# ESP-Power.net
KiCad netlist of a schematic drawn in Altium Designer
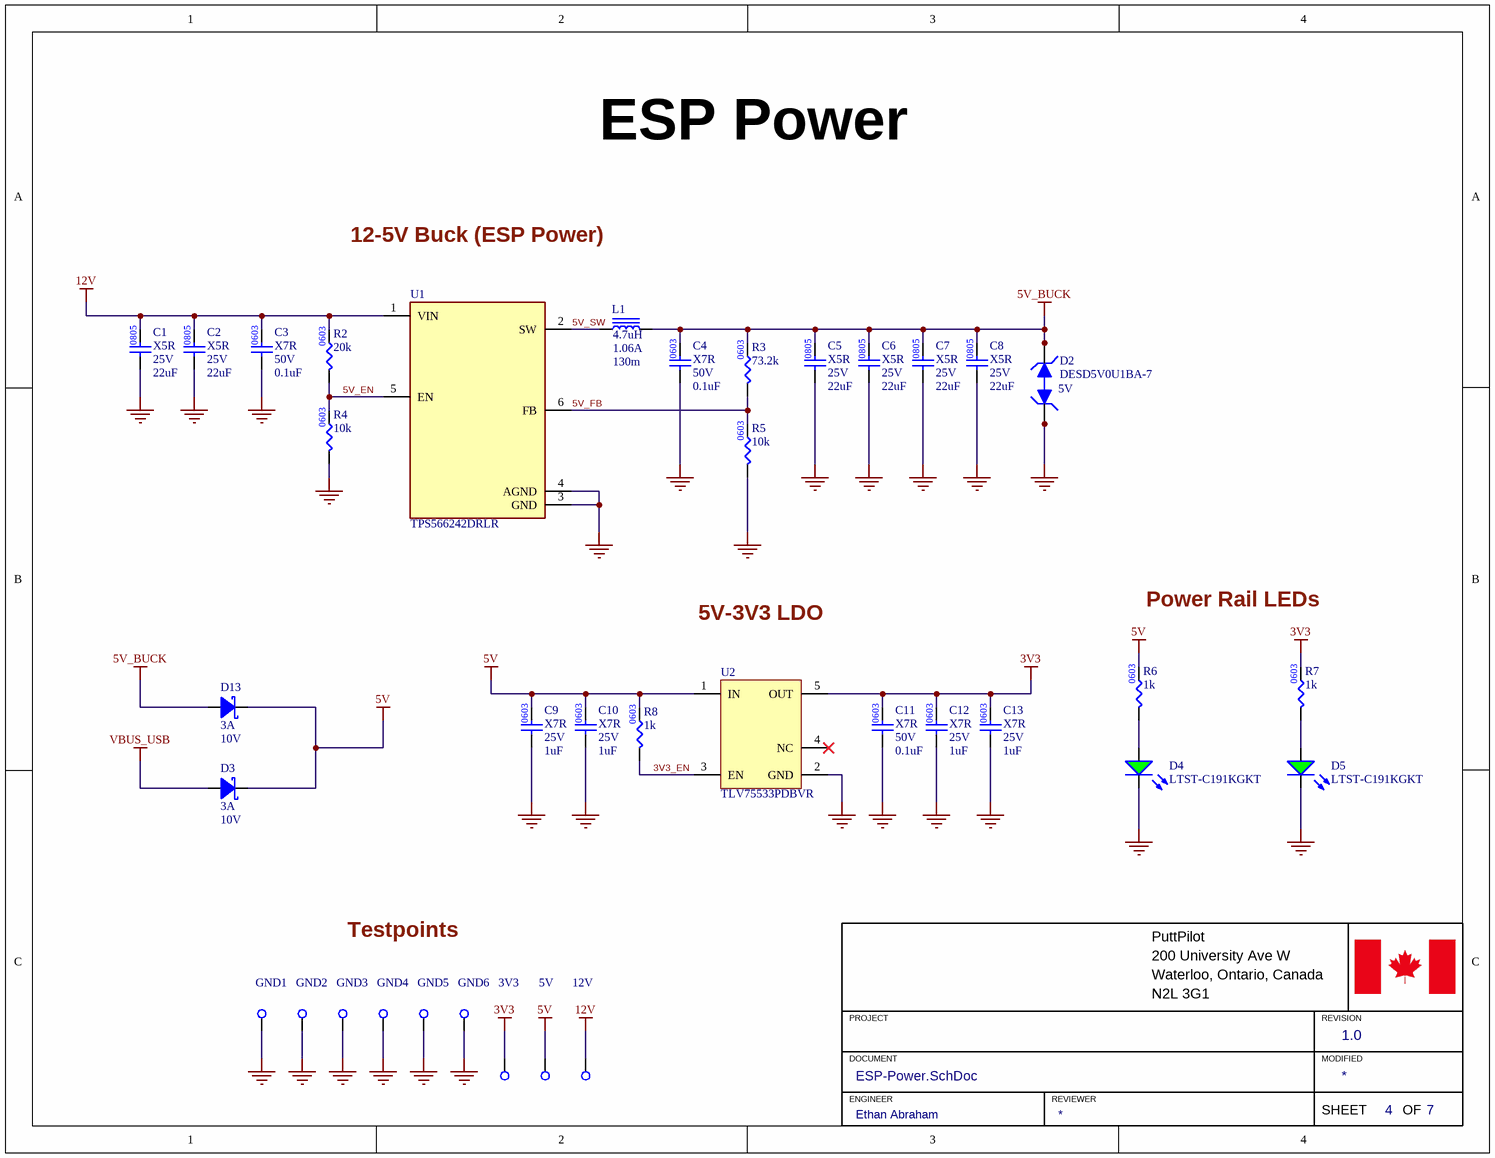
[diagram p0: ESP-Power.SchDoc]

(export (version "E")
  (design (tool "Eeschema 10.0.6"))
  (components
    (comp (ref "3V3")
      (value "RCWCTE")
      (footprint "RCWCTE")
      (description "SMT Test Point")
      (fields (field (name "MANUFACTURER") "KOA Speer"))
      (libsource (lib "PuttPilot") (part "RCWCTE"))
    )
    (comp (ref "5V")
      (value "RCWCTE")
      (footprint "RCWCTE")
      (description "SMT Test Point")
      (fields (field (name "MANUFACTURER") "KOA Speer"))
      (libsource (lib "PuttPilot") (part "RCWCTE"))
    )
    (comp (ref "12V")
      (value "RCWCTE")
      (footprint "RCWCTE")
      (description "SMT Test Point")
      (fields (field (name "MANUFACTURER") "KOA Speer"))
      (libsource (lib "PuttPilot") (part "RCWCTE"))
    )
    (comp (ref "C1")
      (value "GRM21BR61E226ME44K")
      (footprint ".CAP_0805")
      (description "CAP CER 22uF 25V X5R 0805")
      (fields
        (field (name "MANUFACTURER") "Murata")
        (field (name "TEMPERATURE CHARACTERISTICS CODE") "X5R")
        (field (name "RATED DC VOLTAGE (URDC)") "25V")
        (field (name "CAPACITANCE") "22uF")
      )
      (libsource (lib "PuttPilot") (part "GRM21BR61E226ME44K"))
    )
    (comp (ref "C2")
      (value "GRM21BR61E226ME44K")
      (footprint ".CAP_0805")
      (description "CAP CER 22uF 25V X5R 0805")
      (fields
        (field (name "MANUFACTURER") "Murata")
        (field (name "TEMPERATURE CHARACTERISTICS CODE") "X5R")
        (field (name "RATED DC VOLTAGE (URDC)") "25V")
        (field (name "CAPACITANCE") "22uF")
      )
      (libsource (lib "PuttPilot") (part "GRM21BR61E226ME44K"))
    )
    (comp (ref "C3")
      (value "GCJ188R71H104KA12D")
      (footprint ".CAP_0603")
      (description "CAP CER 0.1uF 50V X7R 0603")
      (fields
        (field (name "MANUFACTURER") "Murata")
        (field (name "TEMPERATURE CHARACTERISTICS CODE") "X7R")
        (field (name "RATED DC VOLTAGE (URDC)") "50V")
        (field (name "CAPACITANCE") "0.1uF")
      )
      (libsource (lib "PuttPilot") (part "GCJ188R71H104KA12D"))
    )
    (comp (ref "C4")
      (value "GCJ188R71H104KA12D")
      (footprint ".CAP_0603")
      (description "CAP CER 0.1uF 50V X7R 0603")
      (fields
        (field (name "MANUFACTURER") "Murata")
        (field (name "TEMPERATURE CHARACTERISTICS CODE") "X7R")
        (field (name "RATED DC VOLTAGE (URDC)") "50V")
        (field (name "CAPACITANCE") "0.1uF")
      )
      (libsource (lib "PuttPilot") (part "GCJ188R71H104KA12D"))
    )
    (comp (ref "C5")
      (value "GRM21BR61E226ME44K")
      (footprint ".CAP_0805")
      (description "CAP CER 22uF 25V X5R 0805")
      (fields
        (field (name "MANUFACTURER") "Murata")
        (field (name "TEMPERATURE CHARACTERISTICS CODE") "X5R")
        (field (name "RATED DC VOLTAGE (URDC)") "25V")
        (field (name "CAPACITANCE") "22uF")
      )
      (libsource (lib "PuttPilot") (part "GRM21BR61E226ME44K"))
    )
    (comp (ref "C6")
      (value "GRM21BR61E226ME44K")
      (footprint ".CAP_0805")
      (description "CAP CER 22uF 25V X5R 0805")
      (fields
        (field (name "MANUFACTURER") "Murata")
        (field (name "TEMPERATURE CHARACTERISTICS CODE") "X5R")
        (field (name "RATED DC VOLTAGE (URDC)") "25V")
        (field (name "CAPACITANCE") "22uF")
      )
      (libsource (lib "PuttPilot") (part "GRM21BR61E226ME44K"))
    )
    (comp (ref "C7")
      (value "GRM21BR61E226ME44K")
      (footprint ".CAP_0805")
      (description "CAP CER 22uF 25V X5R 0805")
      (fields
        (field (name "MANUFACTURER") "Murata")
        (field (name "TEMPERATURE CHARACTERISTICS CODE") "X5R")
        (field (name "RATED DC VOLTAGE (URDC)") "25V")
        (field (name "CAPACITANCE") "22uF")
      )
      (libsource (lib "PuttPilot") (part "GRM21BR61E226ME44K"))
    )
    (comp (ref "C8")
      (value "GRM21BR61E226ME44K")
      (footprint ".CAP_0805")
      (description "CAP CER 22uF 25V X5R 0805")
      (fields
        (field (name "MANUFACTURER") "Murata")
        (field (name "TEMPERATURE CHARACTERISTICS CODE") "X5R")
        (field (name "RATED DC VOLTAGE (URDC)") "25V")
        (field (name "CAPACITANCE") "22uF")
      )
      (libsource (lib "PuttPilot") (part "GRM21BR61E226ME44K"))
    )
    (comp (ref "C9")
      (value "GRT188R71E105KE13D")
      (footprint ".CAP_0603")
      (description "CAP CER 1uF 25V X7R 0603")
      (fields
        (field (name "MANUFACTURER") "Murata")
        (field (name "TEMPERATURE CHARACTERISTICS CODE") "X7R")
        (field (name "RATED DC VOLTAGE (URDC)") "25V")
        (field (name "CAPACITANCE") "1uF")
      )
      (libsource (lib "PuttPilot") (part "GRT188R71E105KE13D"))
    )
    (comp (ref "C10")
      (value "GRT188R71E105KE13D")
      (footprint ".CAP_0603")
      (description "CAP CER 1uF 25V X7R 0603")
      (fields
        (field (name "MANUFACTURER") "Murata")
        (field (name "TEMPERATURE CHARACTERISTICS CODE") "X7R")
        (field (name "RATED DC VOLTAGE (URDC)") "25V")
        (field (name "CAPACITANCE") "1uF")
      )
      (libsource (lib "PuttPilot") (part "GRT188R71E105KE13D"))
    )
    (comp (ref "C11")
      (value "GCJ188R71H104KA12D")
      (footprint ".CAP_0603")
      (description "CAP CER 0.1uF 50V X7R 0603")
      (fields
        (field (name "MANUFACTURER") "Murata")
        (field (name "TEMPERATURE CHARACTERISTICS CODE") "X7R")
        (field (name "RATED DC VOLTAGE (URDC)") "50V")
        (field (name "CAPACITANCE") "0.1uF")
      )
      (libsource (lib "PuttPilot") (part "GCJ188R71H104KA12D"))
    )
    (comp (ref "C12")
      (value "GRT188R71E105KE13D")
      (footprint ".CAP_0603")
      (description "CAP CER 1uF 25V X7R 0603")
      (fields
        (field (name "MANUFACTURER") "Murata")
        (field (name "TEMPERATURE CHARACTERISTICS CODE") "X7R")
        (field (name "RATED DC VOLTAGE (URDC)") "25V")
        (field (name "CAPACITANCE") "1uF")
      )
      (libsource (lib "PuttPilot") (part "GRT188R71E105KE13D"))
    )
    (comp (ref "C13")
      (value "GRT188R71E105KE13D")
      (footprint ".CAP_0603")
      (description "CAP CER 1uF 25V X7R 0603")
      (fields
        (field (name "MANUFACTURER") "Murata")
        (field (name "TEMPERATURE CHARACTERISTICS CODE") "X7R")
        (field (name "RATED DC VOLTAGE (URDC)") "25V")
        (field (name "CAPACITANCE") "1uF")
      )
      (libsource (lib "PuttPilot") (part "GRT188R71E105KE13D"))
    )
    (comp (ref "D2")
      (value "DESD5V0U1BA-7")
      (footprint "DESD5V0U1BA-7")
      (description "TVS DIODE 5VWM")
      (fields (field (name "MANUFACTURER") "Diodes") (field (name "REP PK REVERSE VOLTAGE-MAX") "5V"))
      (libsource (lib "PuttPilot") (part "DESD5V0U1BA-7"))
    )
    (comp (ref "D3")
      (value "BAT60JFILM")
      (footprint "BAT60JFILM")
      (description "DIODE SCHOTTKY 10V 3A SOD323")
      (fields (field (name "MAX CURRENT") "3A") (field (name "MAX VOLTAGE") "10V"))
      (libsource (lib "PuttPilot") (part "BAT60JFILM"))
    )
    (comp (ref "D4")
      (value "LTST-C191KGKT")
      (footprint ".LED_0603")
      (description "LED GREEN 2V 0603")
      (fields (field (name "MANUFACTURER") "Vishay Lite-On"))
      (libsource (lib "PuttPilot") (part "LTST-C191KGKT"))
    )
    (comp (ref "D5")
      (value "LTST-C191KGKT")
      (footprint ".LED_0603")
      (description "LED GREEN 2V 0603")
      (fields (field (name "MANUFACTURER") "Vishay Lite-On"))
      (libsource (lib "PuttPilot") (part "LTST-C191KGKT"))
    )
    (comp (ref "D13")
      (value "BAT60JFILM")
      (footprint "BAT60JFILM")
      (description "DIODE SCHOTTKY 10V 3A SOD323")
      (fields (field (name "MAX CURRENT") "3A") (field (name "MAX VOLTAGE") "10V"))
      (libsource (lib "PuttPilot") (part "BAT60JFILM"))
    )
    (comp (ref "GND1")
      (value "RCWCTE")
      (footprint "RCWCTE")
      (description "SMT Test Point")
      (fields (field (name "MANUFACTURER") "KOA Speer"))
      (libsource (lib "PuttPilot") (part "RCWCTE"))
    )
    (comp (ref "GND2")
      (value "RCWCTE")
      (footprint "RCWCTE")
      (description "SMT Test Point")
      (fields (field (name "MANUFACTURER") "KOA Speer"))
      (libsource (lib "PuttPilot") (part "RCWCTE"))
    )
    (comp (ref "GND3")
      (value "RCWCTE")
      (footprint "RCWCTE")
      (description "SMT Test Point")
      (fields (field (name "MANUFACTURER") "KOA Speer"))
      (libsource (lib "PuttPilot") (part "RCWCTE"))
    )
    (comp (ref "GND4")
      (value "RCWCTE")
      (footprint "RCWCTE")
      (description "SMT Test Point")
      (fields (field (name "MANUFACTURER") "KOA Speer"))
      (libsource (lib "PuttPilot") (part "RCWCTE"))
    )
    (comp (ref "GND5")
      (value "RCWCTE")
      (footprint "RCWCTE")
      (description "SMT Test Point")
      (fields (field (name "MANUFACTURER") "KOA Speer"))
      (libsource (lib "PuttPilot") (part "RCWCTE"))
    )
    (comp (ref "GND6")
      (value "RCWCTE")
      (footprint "RCWCTE")
      (description "SMT Test Point")
      (fields (field (name "MANUFACTURER") "KOA Speer"))
      (libsource (lib "PuttPilot") (part "RCWCTE"))
    )
    (comp (ref "L1")
      (value "NRH3012T4R7MN")
      (footprint "NRH3012T4R7MN")
      (description "FIXED IND 4.7uH 1.06A")
      (fields
        (field (name "MANUFACTURER") "Taiyo Yuden")
        (field (name "TOLERANCE") "20%")
        (field (name "DC RESISTANCE (DCR)") "130m")
        (field (name "INDUCTANCE-NOM (L)") "4.7uH")
        (field (name "RATED CURRENT-MAX") "1.06A")
      )
      (libsource (lib "PuttPilot") (part "NRH3012T4R7MN"))
    )
    (comp (ref "R2")
      (value "ERJ-3EKF2002V")
      (footprint ".RES_0603")
      (description "RES 20K OHM 0603")
      (fields
        (field (name "MANUFACTURER") "Panasonic")
        (field (name "TOLERANCE") "1%")
        (field (name "RESISTANCE") "20k")
      )
      (libsource (lib "PuttPilot") (part "ERJ-3EKF2002V"))
    )
    (comp (ref "R3")
      (value "RC0603FR-0773K2L")
      (footprint ".RES_0603")
      (description "RES 73.2K OHM 0603")
      (fields
        (field (name "MANUFACTURER") "Yageo")
        (field (name "TOLERANCE") "1%")
        (field (name "RESISTANCE") "73.2k")
      )
      (libsource (lib "PuttPilot") (part "RC0603FR-0773K2L"))
    )
    (comp (ref "R4")
      (value "RC0603FR-0710KL")
      (footprint ".RES_0603")
      (description "RES 10K OHM 0603")
      (fields
        (field (name "MANUFACTURER") "Yageo")
        (field (name "TOLERANCE") "1%")
        (field (name "RESISTANCE") "10k")
      )
      (libsource (lib "PuttPilot") (part "RC0603FR-0710KL"))
    )
    (comp (ref "R5")
      (value "RC0603FR-0710KL")
      (footprint ".RES_0603")
      (description "RES 10K OHM 0603")
      (fields
        (field (name "MANUFACTURER") "Yageo")
        (field (name "TOLERANCE") "1%")
        (field (name "RESISTANCE") "10k")
      )
      (libsource (lib "PuttPilot") (part "RC0603FR-0710KL"))
    )
    (comp (ref "R6")
      (value "RC0603FR-071KL")
      (footprint ".RES_0603")
      (description "RES 1K OHM 0603")
      (fields
        (field (name "MANUFACTURER") "Yageo")
        (field (name "TOLERANCE") "1%")
        (field (name "RESISTANCE") "1k")
      )
      (libsource (lib "PuttPilot") (part "RC0603FR-071KL"))
    )
    (comp (ref "R7")
      (value "RC0603FR-071KL")
      (footprint ".RES_0603")
      (description "RES 1K OHM 0603")
      (fields
        (field (name "MANUFACTURER") "Yageo")
        (field (name "TOLERANCE") "1%")
        (field (name "RESISTANCE") "1k")
      )
      (libsource (lib "PuttPilot") (part "RC0603FR-071KL"))
    )
    (comp (ref "R8")
      (value "RC0603FR-071KL")
      (footprint ".RES_0603")
      (description "RES 1K OHM 0603")
      (fields
        (field (name "MANUFACTURER") "Yageo")
        (field (name "TOLERANCE") "1%")
        (field (name "RESISTANCE") "1k")
      )
      (libsource (lib "PuttPilot") (part "RC0603FR-071KL"))
    )
    (comp (ref "U1")
      (value "TPS566242DRLR")
      (footprint "TPS566242DRLR")
      (description "BUCK 3V-16V 6A SOT-563")
      (fields (field (name "MANUFACTURER") "Texas Instruments"))
      (libsource (lib "PuttPilot") (part "TPS566242DRLR"))
    )
    (comp (ref "U2")
      (value "TLV75533PDBVR")
      (footprint ".SOT-23-5")
      (description "3V3 (Fixed) LDO 500mA SOT25")
      (fields (field (name "MANUFACTURER") "Texas Instruments"))
      (libsource (lib "PuttPilot") (part "TLV75533PDBVR"))
    )
  )
  (nets
    (net (code "1") (name "/3V3_EN") (class "Default")
      (node (ref "R8") (pin "1") (pinfunction "1_1") (pintype "passive"))
      (node (ref "U2") (pin "3") (pinfunction "EN_3") (pintype "passive"))
    )
    (net (code "2") (name "/5V_EN") (class "Default")
      (node (ref "R2") (pin "1") (pinfunction "1_1") (pintype "passive"))
      (node (ref "R4") (pin "2") (pinfunction "2_2") (pintype "passive"))
      (node (ref "U1") (pin "5") (pinfunction "EN_5") (pintype "passive"))
    )
    (net (code "3") (name "/5V_FB") (class "Default")
      (node (ref "R3") (pin "1") (pinfunction "1_1") (pintype "passive"))
      (node (ref "R5") (pin "2") (pinfunction "2_2") (pintype "passive"))
      (node (ref "U1") (pin "6") (pinfunction "FB_6") (pintype "passive"))
    )
    (net (code "4") (name "/5V_SW") (class "Default")
      (node (ref "L1") (pin "1") (pinfunction "1_1") (pintype "passive"))
      (node (ref "U1") (pin "2") (pinfunction "SW_2") (pintype "passive"))
    )
    (net (code "5") (name "3V3") (class "Default")
      (node (ref "3V3") (pin "1") (pinfunction "1_1") (pintype "passive"))
      (node (ref "C11") (pin "2") (pinfunction "2_2") (pintype "passive"))
      (node (ref "C12") (pin "2") (pinfunction "2_2") (pintype "passive"))
      (node (ref "C13") (pin "2") (pinfunction "2_2") (pintype "passive"))
      (node (ref "R7") (pin "2") (pinfunction "2_2") (pintype "passive"))
      (node (ref "U2") (pin "5") (pinfunction "OUT_5") (pintype "passive"))
    )
    (net (code "6") (name "5V") (class "Default")
      (node (ref "5V") (pin "1") (pinfunction "1_1") (pintype "passive"))
      (node (ref "C10") (pin "2") (pinfunction "2_2") (pintype "passive"))
      (node (ref "C9") (pin "2") (pinfunction "2_2") (pintype "passive"))
      (node (ref "D13") (pin "2") (pinfunction "Cathode_2") (pintype "passive"))
      (node (ref "D3") (pin "2") (pinfunction "Cathode_2") (pintype "passive"))
      (node (ref "R6") (pin "2") (pinfunction "2_2") (pintype "passive"))
      (node (ref "R8") (pin "2") (pinfunction "2_2") (pintype "passive"))
      (node (ref "U2") (pin "1") (pinfunction "IN_1") (pintype "passive"))
    )
    (net (code "7") (name "5V_BUCK") (class "Default")
      (node (ref "C4") (pin "2") (pinfunction "2_2") (pintype "passive"))
      (node (ref "C5") (pin "2") (pinfunction "2_2") (pintype "passive"))
      (node (ref "C6") (pin "2") (pinfunction "2_2") (pintype "passive"))
      (node (ref "C7") (pin "2") (pinfunction "2_2") (pintype "passive"))
      (node (ref "C8") (pin "2") (pinfunction "2_2") (pintype "passive"))
      (node (ref "D13") (pin "1") (pinfunction "Anode_1") (pintype "passive"))
      (node (ref "D2") (pin "2") (pinfunction "Pin_2_2") (pintype "passive"))
      (node (ref "L1") (pin "2") (pinfunction "2_2") (pintype "passive"))
      (node (ref "R3") (pin "2") (pinfunction "2_2") (pintype "passive"))
    )
    (net (code "8") (name "12V") (class "Default")
      (node (ref "12V") (pin "1") (pinfunction "1_1") (pintype "passive"))
      (node (ref "C1") (pin "2") (pinfunction "2_2") (pintype "passive"))
      (node (ref "C2") (pin "2") (pinfunction "2_2") (pintype "passive"))
      (node (ref "C3") (pin "2") (pinfunction "2_2") (pintype "passive"))
      (node (ref "R2") (pin "2") (pinfunction "2_2") (pintype "passive"))
      (node (ref "U1") (pin "1") (pinfunction "VIN_1") (pintype "passive"))
    )
    (net (code "9") (name "GND") (class "Default")
      (node (ref "C1") (pin "1") (pinfunction "1_1") (pintype "passive"))
      (node (ref "C10") (pin "1") (pinfunction "1_1") (pintype "passive"))
      (node (ref "C11") (pin "1") (pinfunction "1_1") (pintype "passive"))
      (node (ref "C12") (pin "1") (pinfunction "1_1") (pintype "passive"))
      (node (ref "C13") (pin "1") (pinfunction "1_1") (pintype "passive"))
      (node (ref "C2") (pin "1") (pinfunction "1_1") (pintype "passive"))
      (node (ref "C3") (pin "1") (pinfunction "1_1") (pintype "passive"))
      (node (ref "C4") (pin "1") (pinfunction "1_1") (pintype "passive"))
      (node (ref "C5") (pin "1") (pinfunction "1_1") (pintype "passive"))
      (node (ref "C6") (pin "1") (pinfunction "1_1") (pintype "passive"))
      (node (ref "C7") (pin "1") (pinfunction "1_1") (pintype "passive"))
      (node (ref "C8") (pin "1") (pinfunction "1_1") (pintype "passive"))
      (node (ref "C9") (pin "1") (pinfunction "1_1") (pintype "passive"))
      (node (ref "D2") (pin "1") (pinfunction "Pin_1_1") (pintype "passive"))
      (node (ref "D4") (pin "2") (pinfunction "K_2") (pintype "passive"))
      (node (ref "D5") (pin "2") (pinfunction "K_2") (pintype "passive"))
      (node (ref "GND1") (pin "1") (pinfunction "1_1") (pintype "passive"))
      (node (ref "GND2") (pin "1") (pinfunction "1_1") (pintype "passive"))
      (node (ref "GND3") (pin "1") (pinfunction "1_1") (pintype "passive"))
      (node (ref "GND4") (pin "1") (pinfunction "1_1") (pintype "passive"))
      (node (ref "GND5") (pin "1") (pinfunction "1_1") (pintype "passive"))
      (node (ref "GND6") (pin "1") (pinfunction "1_1") (pintype "passive"))
      (node (ref "R4") (pin "1") (pinfunction "1_1") (pintype "passive"))
      (node (ref "R5") (pin "1") (pinfunction "1_1") (pintype "passive"))
      (node (ref "U1") (pin "3") (pinfunction "GND_3") (pintype "passive"))
      (node (ref "U1") (pin "4") (pinfunction "AGND_4") (pintype "passive"))
      (node (ref "U2") (pin "2") (pinfunction "GND_2") (pintype "passive"))
    )
    (net (code "10") (name "Net-(D4-A)") (class "Default")
      (node (ref "D4") (pin "1") (pinfunction "A_1") (pintype "passive"))
      (node (ref "R6") (pin "1") (pinfunction "1_1") (pintype "passive"))
    )
    (net (code "11") (name "Net-(D5-A)") (class "Default")
      (node (ref "D5") (pin "1") (pinfunction "A_1") (pintype "passive"))
      (node (ref "R7") (pin "1") (pinfunction "1_1") (pintype "passive"))
    )
    (net (code "12") (name "VBUS_USB") (class "Default")
      (node (ref "D3") (pin "1") (pinfunction "Anode_1") (pintype "passive"))
    )
    (net (code "13") (name "unconnected-(U2-NC-Pad4)") (class "Default")
      (node (ref "U2") (pin "4") (pinfunction "NC_4") (pintype "passive+no_connect"))
    )
  )
)
